# Sheet_2.net
KiCad netlist of a schematic drawn in Altium Designer
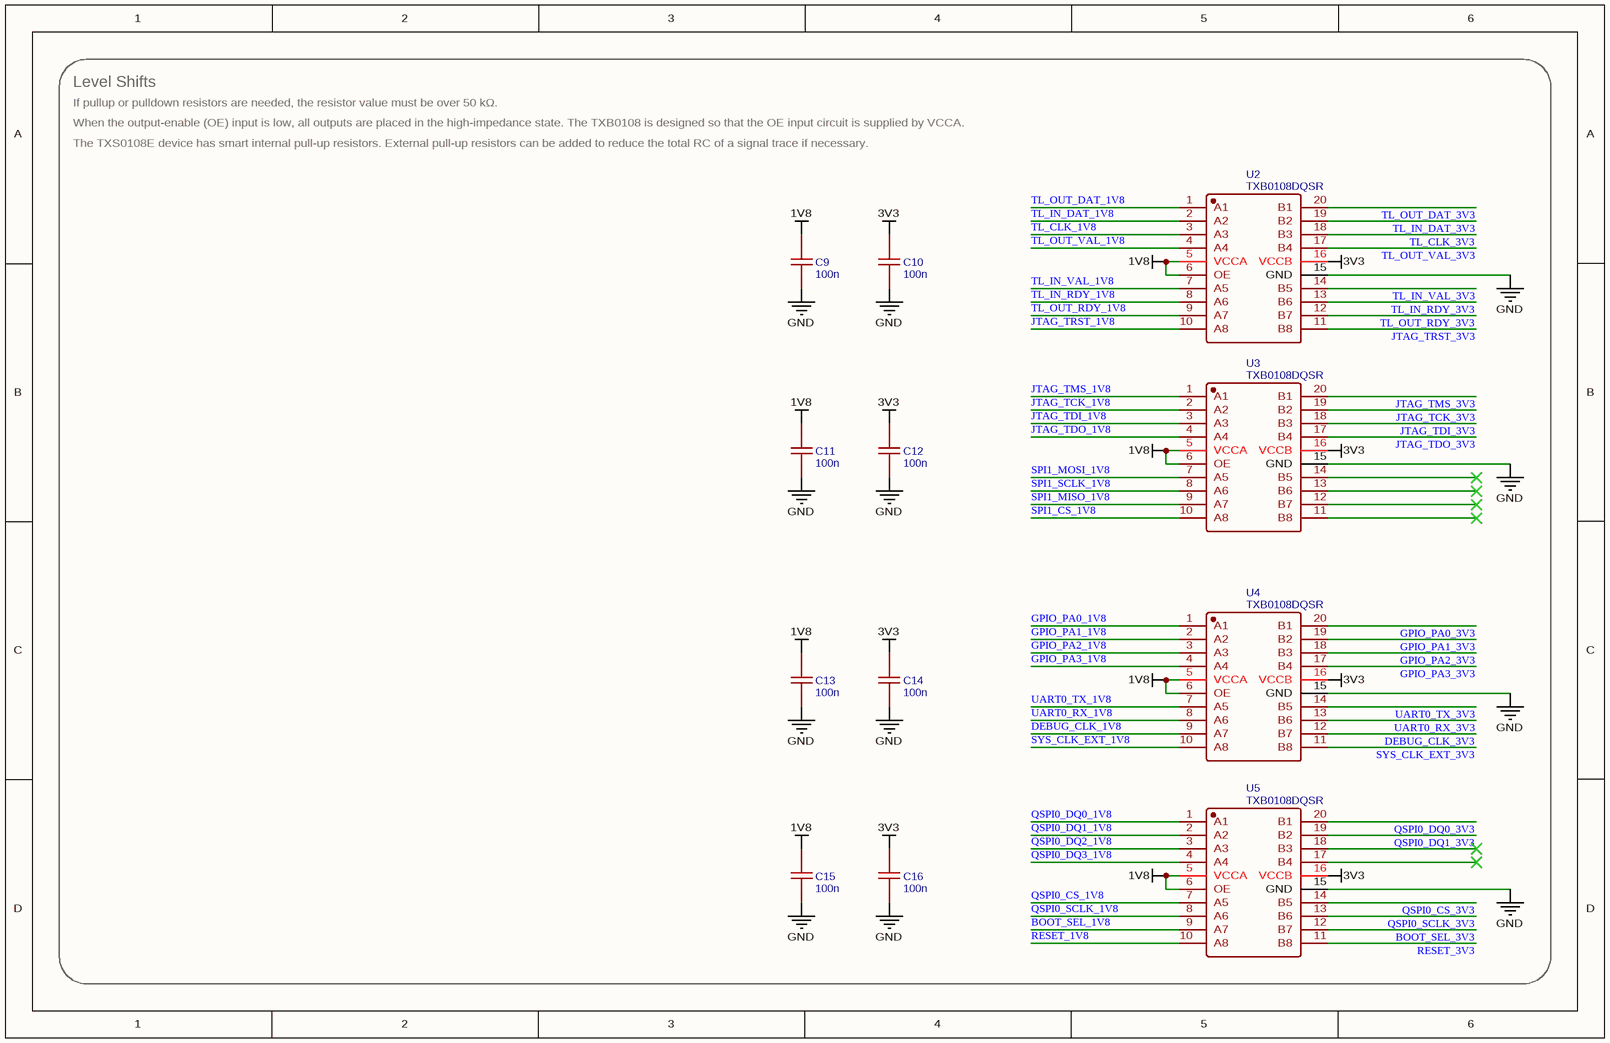
[diagram p0: Sheet_2.schdoc]

(export (version "E")
  (design (tool "Eeschema 10.0.6"))
  (components
    (comp (ref "C9")
      (value "100n")
      (footprint "CAPA-0402")
      (fields
        (field (name "BOM_SUPPLIER PART") "C307331")
        (field (name "BOM_MANUFACTURER PART") "CL05B104KB54PNC")
      )
      (libsource (lib "altium-import") (part "root_1_100n_"))
    )
    (comp (ref "C10")
      (value "100n")
      (footprint "CAPA-0402")
      (fields
        (field (name "BOM_SUPPLIER PART") "C307331")
        (field (name "BOM_MANUFACTURER PART") "CL05B104KB54PNC")
      )
      (libsource (lib "altium-import") (part "root_1_100n_"))
    )
    (comp (ref "C11")
      (value "100n")
      (footprint "CAPA-0402")
      (fields
        (field (name "BOM_SUPPLIER PART") "C307331")
        (field (name "BOM_MANUFACTURER PART") "CL05B104KB54PNC")
      )
      (libsource (lib "altium-import") (part "root_1_100n_"))
    )
    (comp (ref "C12")
      (value "100n")
      (footprint "CAPA-0402")
      (fields
        (field (name "BOM_SUPPLIER PART") "C307331")
        (field (name "BOM_MANUFACTURER PART") "CL05B104KB54PNC")
      )
      (libsource (lib "altium-import") (part "root_1_100n_"))
    )
    (comp (ref "C13")
      (value "100n")
      (footprint "CAPA-0402")
      (fields
        (field (name "BOM_SUPPLIER PART") "C307331")
        (field (name "BOM_MANUFACTURER PART") "CL05B104KB54PNC")
      )
      (libsource (lib "altium-import") (part "root_1_100n_"))
    )
    (comp (ref "C14")
      (value "100n")
      (footprint "CAPA-0402")
      (fields
        (field (name "BOM_SUPPLIER PART") "C307331")
        (field (name "BOM_MANUFACTURER PART") "CL05B104KB54PNC")
      )
      (libsource (lib "altium-import") (part "root_1_100n_"))
    )
    (comp (ref "C15")
      (value "100n")
      (footprint "CAPA-0402")
      (fields
        (field (name "BOM_SUPPLIER PART") "C307331")
        (field (name "BOM_MANUFACTURER PART") "CL05B104KB54PNC")
      )
      (libsource (lib "altium-import") (part "root_1_100n_"))
    )
    (comp (ref "C16")
      (value "100n")
      (footprint "CAPA-0402")
      (fields
        (field (name "BOM_SUPPLIER PART") "C307331")
        (field (name "BOM_MANUFACTURER PART") "CL05B104KB54PNC")
      )
      (libsource (lib "altium-import") (part "root_1_100n_"))
    )
    (comp (ref "U2")
      (value "TXB0108DQSR")
      (footprint "SON-20_L4.0-W2.0-P0.40-BL")
      (fields (field (name "BOM_SUPPLIER PART") "C427057"))
      (libsource (lib "altium-import") (part "root_0_TXB0108DQSR_"))
    )
    (comp (ref "U3")
      (value "TXB0108DQSR")
      (footprint "SON-20_L4.0-W2.0-P0.40-BL")
      (fields (field (name "BOM_SUPPLIER PART") "C427057"))
      (libsource (lib "altium-import") (part "root_0_TXB0108DQSR_"))
    )
    (comp (ref "U4")
      (value "TXB0108DQSR")
      (footprint "SON-20_L4.0-W2.0-P0.40-BL")
      (fields (field (name "BOM_SUPPLIER PART") "C427057"))
      (libsource (lib "altium-import") (part "root_0_TXB0108DQSR_"))
    )
    (comp (ref "U5")
      (value "TXB0108DQSR")
      (footprint "SON-20_L4.0-W2.0-P0.40-BL")
      (fields (field (name "BOM_SUPPLIER PART") "C427057"))
      (libsource (lib "altium-import") (part "root_0_TXB0108DQSR_"))
    )
  )
  (nets
    (net (code "1") (name "/BOOT_SEL_1V8") (class "Default")
      (node (ref "U5") (pin "9") (pinfunction "A7_9") (pintype "passive"))
    )
    (net (code "2") (name "/BOOT_SEL_3V3") (class "Default")
      (node (ref "U5") (pin "12") (pinfunction "B7_12") (pintype "passive"))
    )
    (net (code "3") (name "/DEBUG_CLK_1V8") (class "Default")
      (node (ref "U4") (pin "9") (pinfunction "A7_9") (pintype "passive"))
    )
    (net (code "4") (name "/DEBUG_CLK_3V3") (class "Default")
      (node (ref "U4") (pin "12") (pinfunction "B7_12") (pintype "passive"))
    )
    (net (code "5") (name "/GPIO_PA0_1V8") (class "Default")
      (node (ref "U4") (pin "1") (pinfunction "A1_1") (pintype "passive"))
    )
    (net (code "6") (name "/GPIO_PA0_3V3") (class "Default")
      (node (ref "U4") (pin "20") (pinfunction "B1_20") (pintype "passive"))
    )
    (net (code "7") (name "/GPIO_PA1_1V8") (class "Default")
      (node (ref "U4") (pin "2") (pinfunction "A2_2") (pintype "passive"))
    )
    (net (code "8") (name "/GPIO_PA1_3V3") (class "Default")
      (node (ref "U4") (pin "19") (pinfunction "B2_19") (pintype "passive"))
    )
    (net (code "9") (name "/GPIO_PA2_1V8") (class "Default")
      (node (ref "U4") (pin "3") (pinfunction "A3_3") (pintype "passive"))
    )
    (net (code "10") (name "/GPIO_PA2_3V3") (class "Default")
      (node (ref "U4") (pin "18") (pinfunction "B3_18") (pintype "passive"))
    )
    (net (code "11") (name "/GPIO_PA3_1V8") (class "Default")
      (node (ref "U4") (pin "4") (pinfunction "A4_4") (pintype "passive"))
    )
    (net (code "12") (name "/GPIO_PA3_3V3") (class "Default")
      (node (ref "U4") (pin "17") (pinfunction "B4_17") (pintype "passive"))
    )
    (net (code "13") (name "/JTAG_TCK_1V8") (class "Default")
      (node (ref "U3") (pin "2") (pinfunction "A2_2") (pintype "passive"))
    )
    (net (code "14") (name "/JTAG_TCK_3V3") (class "Default")
      (node (ref "U3") (pin "19") (pinfunction "B2_19") (pintype "passive"))
    )
    (net (code "15") (name "/JTAG_TDI_1V8") (class "Default")
      (node (ref "U3") (pin "3") (pinfunction "A3_3") (pintype "passive"))
    )
    (net (code "16") (name "/JTAG_TDI_3V3") (class "Default")
      (node (ref "U3") (pin "18") (pinfunction "B3_18") (pintype "passive"))
    )
    (net (code "17") (name "/JTAG_TDO_1V8") (class "Default")
      (node (ref "U3") (pin "4") (pinfunction "A4_4") (pintype "passive"))
    )
    (net (code "18") (name "/JTAG_TDO_3V3") (class "Default")
      (node (ref "U3") (pin "17") (pinfunction "B4_17") (pintype "passive"))
    )
    (net (code "19") (name "/JTAG_TMS_1V8") (class "Default")
      (node (ref "U3") (pin "1") (pinfunction "A1_1") (pintype "passive"))
    )
    (net (code "20") (name "/JTAG_TMS_3V3") (class "Default")
      (node (ref "U3") (pin "20") (pinfunction "B1_20") (pintype "passive"))
    )
    (net (code "21") (name "/JTAG_TRST_1V8") (class "Default")
      (node (ref "U2") (pin "10") (pinfunction "A8_10") (pintype "passive"))
    )
    (net (code "22") (name "/JTAG_TRST_3V3") (class "Default")
      (node (ref "U2") (pin "11") (pinfunction "B8_11") (pintype "passive"))
    )
    (net (code "23") (name "/QSPI0_CS_1V8") (class "Default")
      (node (ref "U5") (pin "7") (pinfunction "A5_7") (pintype "passive"))
    )
    (net (code "24") (name "/QSPI0_CS_3V3") (class "Default")
      (node (ref "U5") (pin "14") (pinfunction "B5_14") (pintype "passive"))
    )
    (net (code "25") (name "/QSPI0_DQ0_1V8") (class "Default")
      (node (ref "U5") (pin "1") (pinfunction "A1_1") (pintype "passive"))
    )
    (net (code "26") (name "/QSPI0_DQ0_3V3") (class "Default")
      (node (ref "U5") (pin "20") (pinfunction "B1_20") (pintype "passive"))
    )
    (net (code "27") (name "/QSPI0_DQ1_1V8") (class "Default")
      (node (ref "U5") (pin "2") (pinfunction "A2_2") (pintype "passive"))
    )
    (net (code "28") (name "/QSPI0_DQ1_3V3") (class "Default")
      (node (ref "U5") (pin "19") (pinfunction "B2_19") (pintype "passive"))
    )
    (net (code "29") (name "/QSPI0_DQ2_1V8") (class "Default")
      (node (ref "U5") (pin "3") (pinfunction "A3_3") (pintype "passive"))
    )
    (net (code "30") (name "/QSPI0_DQ3_1V8") (class "Default")
      (node (ref "U5") (pin "4") (pinfunction "A4_4") (pintype "passive"))
    )
    (net (code "31") (name "/QSPI0_SCLK_1V8") (class "Default")
      (node (ref "U5") (pin "8") (pinfunction "A6_8") (pintype "passive"))
    )
    (net (code "32") (name "/QSPI0_SCLK_3V3") (class "Default")
      (node (ref "U5") (pin "13") (pinfunction "B6_13") (pintype "passive"))
    )
    (net (code "33") (name "/RESET_1V8") (class "Default")
      (node (ref "U5") (pin "10") (pinfunction "A8_10") (pintype "passive"))
    )
    (net (code "34") (name "/RESET_3V3") (class "Default")
      (node (ref "U5") (pin "11") (pinfunction "B8_11") (pintype "passive"))
    )
    (net (code "35") (name "/SPI1_CS_1V8") (class "Default")
      (node (ref "U3") (pin "10") (pinfunction "A8_10") (pintype "passive"))
    )
    (net (code "36") (name "/SPI1_MISO_1V8") (class "Default")
      (node (ref "U3") (pin "9") (pinfunction "A7_9") (pintype "passive"))
    )
    (net (code "37") (name "/SPI1_MOSI_1V8") (class "Default")
      (node (ref "U3") (pin "7") (pinfunction "A5_7") (pintype "passive"))
    )
    (net (code "38") (name "/SPI1_SCLK_1V8") (class "Default")
      (node (ref "U3") (pin "8") (pinfunction "A6_8") (pintype "passive"))
    )
    (net (code "39") (name "/SYS_CLK_EXT_1V8") (class "Default")
      (node (ref "U4") (pin "10") (pinfunction "A8_10") (pintype "passive"))
    )
    (net (code "40") (name "/SYS_CLK_EXT_3V3") (class "Default")
      (node (ref "U4") (pin "11") (pinfunction "B8_11") (pintype "passive"))
    )
    (net (code "41") (name "/TL_CLK_1V8") (class "Default")
      (node (ref "U2") (pin "3") (pinfunction "A3_3") (pintype "passive"))
    )
    (net (code "42") (name "/TL_CLK_3V3") (class "Default")
      (node (ref "U2") (pin "18") (pinfunction "B3_18") (pintype "passive"))
    )
    (net (code "43") (name "/TL_IN_DAT_1V8") (class "Default")
      (node (ref "U2") (pin "2") (pinfunction "A2_2") (pintype "passive"))
    )
    (net (code "44") (name "/TL_IN_DAT_3V3") (class "Default")
      (node (ref "U2") (pin "19") (pinfunction "B2_19") (pintype "passive"))
    )
    (net (code "45") (name "/TL_IN_RDY_1V8") (class "Default")
      (node (ref "U2") (pin "8") (pinfunction "A6_8") (pintype "passive"))
    )
    (net (code "46") (name "/TL_IN_RDY_3V3") (class "Default")
      (node (ref "U2") (pin "13") (pinfunction "B6_13") (pintype "passive"))
    )
    (net (code "47") (name "/TL_IN_VAL_1V8") (class "Default")
      (node (ref "U2") (pin "7") (pinfunction "A5_7") (pintype "passive"))
    )
    (net (code "48") (name "/TL_IN_VAL_3V3") (class "Default")
      (node (ref "U2") (pin "14") (pinfunction "B5_14") (pintype "passive"))
    )
    (net (code "49") (name "/TL_OUT_DAT_1V8") (class "Default")
      (node (ref "U2") (pin "1") (pinfunction "A1_1") (pintype "passive"))
    )
    (net (code "50") (name "/TL_OUT_DAT_3V3") (class "Default")
      (node (ref "U2") (pin "20") (pinfunction "B1_20") (pintype "passive"))
    )
    (net (code "51") (name "/TL_OUT_RDY_1V8") (class "Default")
      (node (ref "U2") (pin "9") (pinfunction "A7_9") (pintype "passive"))
    )
    (net (code "52") (name "/TL_OUT_RDY_3V3") (class "Default")
      (node (ref "U2") (pin "12") (pinfunction "B7_12") (pintype "passive"))
    )
    (net (code "53") (name "/TL_OUT_VAL_1V8") (class "Default")
      (node (ref "U2") (pin "4") (pinfunction "A4_4") (pintype "passive"))
    )
    (net (code "54") (name "/TL_OUT_VAL_3V3") (class "Default")
      (node (ref "U2") (pin "17") (pinfunction "B4_17") (pintype "passive"))
    )
    (net (code "55") (name "/UART0_RX_1V8") (class "Default")
      (node (ref "U4") (pin "8") (pinfunction "A6_8") (pintype "passive"))
    )
    (net (code "56") (name "/UART0_RX_3V3") (class "Default")
      (node (ref "U4") (pin "13") (pinfunction "B6_13") (pintype "passive"))
    )
    (net (code "57") (name "/UART0_TX_1V8") (class "Default")
      (node (ref "U4") (pin "7") (pinfunction "A5_7") (pintype "passive"))
    )
    (net (code "58") (name "/UART0_TX_3V3") (class "Default")
      (node (ref "U4") (pin "14") (pinfunction "B5_14") (pintype "passive"))
    )
    (net (code "59") (name "1V8") (class "Default")
      (node (ref "C11") (pin "2") (pinfunction "2_2") (pintype "passive"))
      (node (ref "C13") (pin "2") (pinfunction "2_2") (pintype "passive"))
      (node (ref "C15") (pin "2") (pinfunction "2_2") (pintype "passive"))
      (node (ref "C9") (pin "2") (pinfunction "2_2") (pintype "passive"))
      (node (ref "U2") (pin "5") (pinfunction "VCCA_5") (pintype "passive"))
      (node (ref "U2") (pin "6") (pinfunction "OE_6") (pintype "passive"))
      (node (ref "U3") (pin "5") (pinfunction "VCCA_5") (pintype "passive"))
      (node (ref "U3") (pin "6") (pinfunction "OE_6") (pintype "passive"))
      (node (ref "U4") (pin "5") (pinfunction "VCCA_5") (pintype "passive"))
      (node (ref "U4") (pin "6") (pinfunction "OE_6") (pintype "passive"))
      (node (ref "U5") (pin "5") (pinfunction "VCCA_5") (pintype "passive"))
      (node (ref "U5") (pin "6") (pinfunction "OE_6") (pintype "passive"))
    )
    (net (code "60") (name "3V3") (class "Default")
      (node (ref "C10") (pin "2") (pinfunction "2_2") (pintype "passive"))
      (node (ref "C12") (pin "2") (pinfunction "2_2") (pintype "passive"))
      (node (ref "C14") (pin "2") (pinfunction "2_2") (pintype "passive"))
      (node (ref "C16") (pin "2") (pinfunction "2_2") (pintype "passive"))
      (node (ref "U2") (pin "16") (pinfunction "VCCB_16") (pintype "passive"))
      (node (ref "U3") (pin "16") (pinfunction "VCCB_16") (pintype "passive"))
      (node (ref "U4") (pin "16") (pinfunction "VCCB_16") (pintype "passive"))
      (node (ref "U5") (pin "16") (pinfunction "VCCB_16") (pintype "passive"))
    )
    (net (code "61") (name "GND") (class "Default")
      (node (ref "C10") (pin "1") (pinfunction "1_1") (pintype "passive"))
      (node (ref "C11") (pin "1") (pinfunction "1_1") (pintype "passive"))
      (node (ref "C12") (pin "1") (pinfunction "1_1") (pintype "passive"))
      (node (ref "C13") (pin "1") (pinfunction "1_1") (pintype "passive"))
      (node (ref "C14") (pin "1") (pinfunction "1_1") (pintype "passive"))
      (node (ref "C15") (pin "1") (pinfunction "1_1") (pintype "passive"))
      (node (ref "C16") (pin "1") (pinfunction "1_1") (pintype "passive"))
      (node (ref "C9") (pin "1") (pinfunction "1_1") (pintype "passive"))
      (node (ref "U2") (pin "15") (pinfunction "GND_15") (pintype "passive"))
      (node (ref "U3") (pin "15") (pinfunction "GND_15") (pintype "passive"))
      (node (ref "U4") (pin "15") (pinfunction "GND_15") (pintype "passive"))
      (node (ref "U5") (pin "15") (pinfunction "GND_15") (pintype "passive"))
    )
    (net (code "62") (name "unconnected-(U3-B5-Pad14)") (class "Default")
      (node (ref "U3") (pin "14") (pinfunction "B5_14") (pintype "passive+no_connect"))
    )
    (net (code "63") (name "unconnected-(U3-B6-Pad13)") (class "Default")
      (node (ref "U3") (pin "13") (pinfunction "B6_13") (pintype "passive+no_connect"))
    )
    (net (code "64") (name "unconnected-(U3-B7-Pad12)") (class "Default")
      (node (ref "U3") (pin "12") (pinfunction "B7_12") (pintype "passive+no_connect"))
    )
    (net (code "65") (name "unconnected-(U3-B8-Pad11)") (class "Default")
      (node (ref "U3") (pin "11") (pinfunction "B8_11") (pintype "passive+no_connect"))
    )
    (net (code "66") (name "unconnected-(U5-B3-Pad18)") (class "Default")
      (node (ref "U5") (pin "18") (pinfunction "B3_18") (pintype "passive+no_connect"))
    )
    (net (code "67") (name "unconnected-(U5-B4-Pad17)") (class "Default")
      (node (ref "U5") (pin "17") (pinfunction "B4_17") (pintype "passive+no_connect"))
    )
  )
)
